# 5_motor_driver.net
KiCad netlist of a schematic drawn in Altium Designer
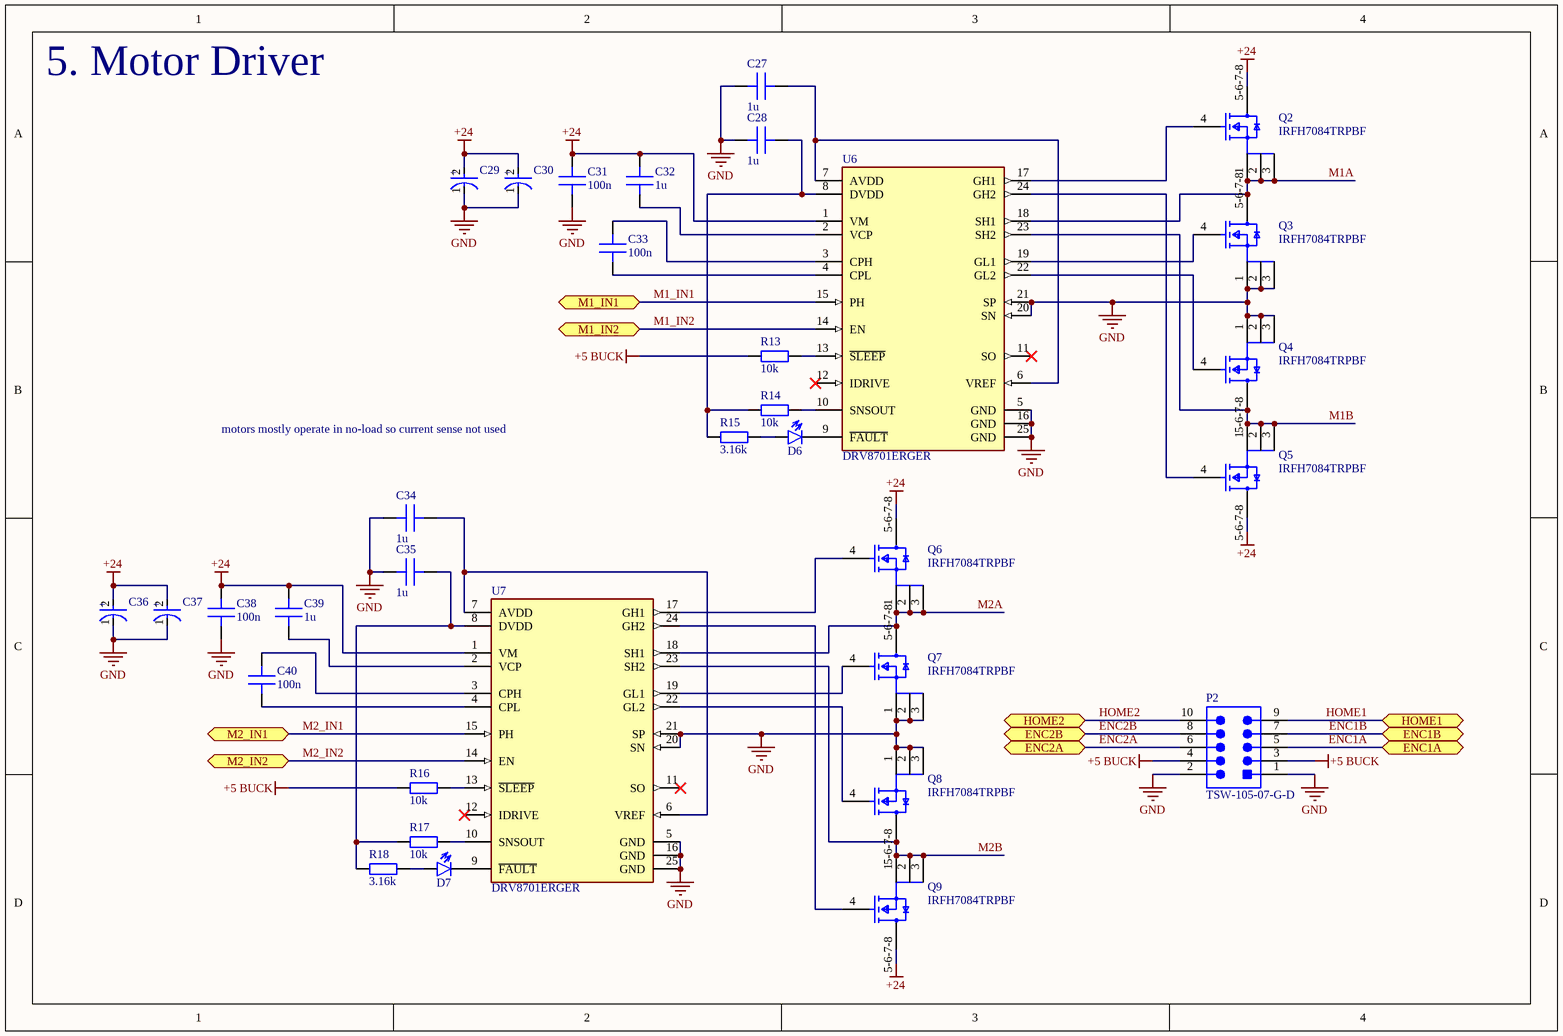
[diagram p0: 5_motor driver.SchDoc]

(export (version "E")
  (design (tool "Eeschema 10.0.6"))
  (components
    (comp (ref "C27")
      (value "1u")
      (footprint "IPC C C0402 NO SILK")
      (libsource (lib "JLCPCB Library") (part "Generic CAP 0402"))
    )
    (comp (ref "C28")
      (value "1u")
      (footprint "IPC C C0402 NO SILK")
      (libsource (lib "JLCPCB Library") (part "Generic CAP 0402"))
    )
    (comp (ref "C29")
      (value "UCW1H221MNL1GS")
      (footprint "FP-UCW1H221MNL1GS-MFG")
      (description "CAP ALUM 220UF 20% 50V SMD")
      (fields (field (name "TOLERANCE") "20%") (field (name "VOLTAGE") "50V"))
      (libsource (lib "Altium Content Vault") (part "cf48714ba7e38822c1575c7ec0b6d1f"))
    )
    (comp (ref "C30")
      (value "UCW1H221MNL1GS")
      (footprint "FP-UCW1H221MNL1GS-MFG")
      (description "CAP ALUM 220UF 20% 50V SMD")
      (fields (field (name "TOLERANCE") "20%") (field (name "VOLTAGE") "50V"))
      (libsource (lib "Altium Content Vault") (part "cf48714ba7e38822c1575c7ec0b6d1f"))
    )
    (comp (ref "C31")
      (value "100n")
      (footprint "IPC C C0603 NO SILK")
      (libsource (lib "JLCPCB Library") (part "Generic CAP 0603"))
    )
    (comp (ref "C32")
      (value "1u")
      (footprint "IPC C C0603 NO SILK")
      (libsource (lib "JLCPCB Library") (part "Generic CAP 0603"))
    )
    (comp (ref "C33")
      (value "100n")
      (footprint "IPC C C0603 NO SILK")
      (libsource (lib "JLCPCB Library") (part "Generic CAP 0603"))
    )
    (comp (ref "C34")
      (value "1u")
      (footprint "IPC C C0402 NO SILK")
      (libsource (lib "JLCPCB Library") (part "Generic CAP 0402"))
    )
    (comp (ref "C35")
      (value "1u")
      (footprint "IPC C C0402 NO SILK")
      (libsource (lib "JLCPCB Library") (part "Generic CAP 0402"))
    )
    (comp (ref "C36")
      (value "UCW1H221MNL1GS")
      (footprint "FP-UCW1H221MNL1GS-MFG")
      (description "CAP ALUM 220UF 20% 50V SMD")
      (fields (field (name "TOLERANCE") "20%") (field (name "VOLTAGE") "50V"))
      (libsource (lib "Altium Content Vault") (part "cf48714ba7e38822c1575c7ec0b6d1f"))
    )
    (comp (ref "C37")
      (value "UCW1H221MNL1GS")
      (footprint "FP-UCW1H221MNL1GS-MFG")
      (description "CAP ALUM 220UF 20% 50V SMD")
      (fields (field (name "TOLERANCE") "20%") (field (name "VOLTAGE") "50V"))
      (libsource (lib "Altium Content Vault") (part "cf48714ba7e38822c1575c7ec0b6d1f"))
    )
    (comp (ref "C38")
      (value "100n")
      (footprint "IPC C C0603 NO SILK")
      (libsource (lib "JLCPCB Library") (part "Generic CAP 0603"))
    )
    (comp (ref "C39")
      (value "1u")
      (footprint "IPC C C0603 NO SILK")
      (libsource (lib "JLCPCB Library") (part "Generic CAP 0603"))
    )
    (comp (ref "C40")
      (value "100n")
      (footprint "IPC C C0603 NO SILK")
      (libsource (lib "JLCPCB Library") (part "Generic CAP 0603"))
    )
    (comp (ref "D6")
      (value "Red LED 0603")
      (footprint "IPC C D0603")
      (libsource (lib "JLCPCB Library") (part "Generic LED 0603"))
    )
    (comp (ref "D7")
      (value "Red LED 0603")
      (footprint "IPC C D0603")
      (libsource (lib "JLCPCB Library") (part "Generic LED 0603"))
    )
    (comp (ref "P2")
      (value "TSW-105-07-G-D")
      (footprint "SMTC-TSW-105-07-G-D_V")
      (fields (field (name "MANUFACTURER") "Samtec-Inc."))
      (libsource (lib "Altium Content Vault") (part "CN-2P-M-R10"))
    )
    (comp (ref "Q2")
      (value "IRFH7084TRPBF")
      (footprint "FP-PQFN5x6-G-MFG")
      (description "MOSFET N-CH 40V 100A 8QFN")
      (libsource (lib "Altium Content Vault") (part "95ca5d46c4c8fe7d84c4fb5e2abfe3c"))
    )
    (comp (ref "Q3")
      (value "IRFH7084TRPBF")
      (footprint "FP-PQFN5x6-G-MFG")
      (description "MOSFET N-CH 40V 100A 8QFN")
      (libsource (lib "Altium Content Vault") (part "95ca5d46c4c8fe7d84c4fb5e2abfe3c"))
    )
    (comp (ref "Q4")
      (value "IRFH7084TRPBF")
      (footprint "FP-PQFN5x6-G-MFG")
      (description "MOSFET N-CH 40V 100A 8QFN")
      (libsource (lib "Altium Content Vault") (part "95ca5d46c4c8fe7d84c4fb5e2abfe3c"))
    )
    (comp (ref "Q5")
      (value "IRFH7084TRPBF")
      (footprint "FP-PQFN5x6-G-MFG")
      (description "MOSFET N-CH 40V 100A 8QFN")
      (libsource (lib "Altium Content Vault") (part "95ca5d46c4c8fe7d84c4fb5e2abfe3c"))
    )
    (comp (ref "Q6")
      (value "IRFH7084TRPBF")
      (footprint "FP-PQFN5x6-G-MFG")
      (description "MOSFET N-CH 40V 100A 8QFN")
      (libsource (lib "Altium Content Vault") (part "95ca5d46c4c8fe7d84c4fb5e2abfe3c"))
    )
    (comp (ref "Q7")
      (value "IRFH7084TRPBF")
      (footprint "FP-PQFN5x6-G-MFG")
      (description "MOSFET N-CH 40V 100A 8QFN")
      (libsource (lib "Altium Content Vault") (part "95ca5d46c4c8fe7d84c4fb5e2abfe3c"))
    )
    (comp (ref "Q8")
      (value "IRFH7084TRPBF")
      (footprint "FP-PQFN5x6-G-MFG")
      (description "MOSFET N-CH 40V 100A 8QFN")
      (libsource (lib "Altium Content Vault") (part "95ca5d46c4c8fe7d84c4fb5e2abfe3c"))
    )
    (comp (ref "Q9")
      (value "IRFH7084TRPBF")
      (footprint "FP-PQFN5x6-G-MFG")
      (description "MOSFET N-CH 40V 100A 8QFN")
      (libsource (lib "Altium Content Vault") (part "95ca5d46c4c8fe7d84c4fb5e2abfe3c"))
    )
    (comp (ref "R13")
      (value "10k")
      (footprint "IPC C R0402 NO SILK")
      (libsource (lib "JLCPCB Library") (part "Generic RES 0402"))
    )
    (comp (ref "R14")
      (value "10k")
      (footprint "IPC C R0402 NO SILK")
      (libsource (lib "JLCPCB Library") (part "Generic RES 0402"))
    )
    (comp (ref "R15")
      (value "3.16k")
      (footprint "IPC C R0402 NO SILK")
      (libsource (lib "JLCPCB Library") (part "Generic RES 0402"))
    )
    (comp (ref "R16")
      (value "10k")
      (footprint "IPC C R0402 NO SILK")
      (libsource (lib "JLCPCB Library") (part "Generic RES 0402"))
    )
    (comp (ref "R17")
      (value "10k")
      (footprint "IPC C R0402 NO SILK")
      (libsource (lib "JLCPCB Library") (part "Generic RES 0402"))
    )
    (comp (ref "R18")
      (value "3.16k")
      (footprint "IPC C R0402 NO SILK")
      (libsource (lib "JLCPCB Library") (part "Generic RES 0402"))
    )
    (comp (ref "U6")
      (value "DRV8701ERGER")
      (footprint "FP-RGE0024F-MFG")
      (description "IC MOTOR DRIVER 0V-5.5V 24VQFN")
      (libsource (lib "Altium Content Vault") (part "52b49e6391ebd4280530f99f160d6ab"))
    )
    (comp (ref "U7")
      (value "DRV8701ERGER")
      (footprint "FP-RGE0024F-MFG")
      (description "IC MOTOR DRIVER 0V-5.5V 24VQFN")
      (libsource (lib "Altium Content Vault") (part "52b49e6391ebd4280530f99f160d6ab"))
    )
  )
  (nets
    (net (code "1") (name "+5 BUCK") (class "Default")
      (node (ref "P2") (pin "3") (pinfunction "3_3") (pintype "passive"))
      (node (ref "P2") (pin "4") (pinfunction "4_4") (pintype "passive"))
      (node (ref "R13") (pin "2") (pinfunction "2_2") (pintype "passive"))
      (node (ref "R16") (pin "2") (pinfunction "2_2") (pintype "passive"))
    )
    (net (code "2") (name "+24") (class "Default")
      (node (ref "C29") (pin "2") (pinfunction "A_2") (pintype "passive"))
      (node (ref "C30") (pin "2") (pinfunction "A_2") (pintype "passive"))
      (node (ref "C31") (pin "2") (pinfunction "2_2") (pintype "passive"))
      (node (ref "C32") (pin "1") (pinfunction "1_1") (pintype "passive"))
      (node (ref "C36") (pin "2") (pinfunction "A_2") (pintype "passive"))
      (node (ref "C37") (pin "2") (pinfunction "A_2") (pintype "passive"))
      (node (ref "C38") (pin "2") (pinfunction "2_2") (pintype "passive"))
      (node (ref "C39") (pin "1") (pinfunction "1_1") (pintype "passive"))
      (node (ref "Q2") (pin "5-6-7-8") (pinfunction "D_5-6-7-8") (pintype "passive"))
      (node (ref "Q5") (pin "5-6-7-8") (pinfunction "D_5-6-7-8") (pintype "passive"))
      (node (ref "Q6") (pin "5-6-7-8") (pinfunction "D_5-6-7-8") (pintype "passive"))
      (node (ref "Q9") (pin "5-6-7-8") (pinfunction "D_5-6-7-8") (pintype "passive"))
      (node (ref "U6") (pin "1") (pinfunction "VM_1") (pintype "power_in"))
      (node (ref "U7") (pin "1") (pinfunction "VM_1") (pintype "power_in"))
    )
    (net (code "3") (name "/ENC1A") (class "Default")
      (node (ref "P2") (pin "5") (pinfunction "5_5") (pintype "passive"))
    )
    (net (code "4") (name "/ENC1B") (class "Default")
      (node (ref "P2") (pin "7") (pinfunction "7_7") (pintype "passive"))
    )
    (net (code "5") (name "/ENC2A") (class "Default")
      (node (ref "P2") (pin "6") (pinfunction "6_6") (pintype "passive"))
    )
    (net (code "6") (name "/ENC2B") (class "Default")
      (node (ref "P2") (pin "8") (pinfunction "8_8") (pintype "passive"))
    )
    (net (code "7") (name "/HOME1") (class "Default")
      (node (ref "P2") (pin "9") (pinfunction "9_9") (pintype "passive"))
    )
    (net (code "8") (name "/HOME2") (class "Default")
      (node (ref "P2") (pin "10") (pinfunction "10_10") (pintype "passive"))
    )
    (net (code "9") (name "/M1A") (class "Default")
      (node (ref "Q2") (pin "1") (pinfunction "S_1") (pintype "passive"))
      (node (ref "Q2") (pin "2") (pinfunction "S_2") (pintype "passive"))
      (node (ref "Q2") (pin "3") (pinfunction "S_3") (pintype "passive"))
      (node (ref "Q3") (pin "5-6-7-8") (pinfunction "D_5-6-7-8") (pintype "passive"))
      (node (ref "U6") (pin "18") (pinfunction "SH1_18") (pintype "output"))
    )
    (net (code "10") (name "/M1B") (class "Default")
      (node (ref "Q4") (pin "5-6-7-8") (pinfunction "D_5-6-7-8") (pintype "passive"))
      (node (ref "Q5") (pin "1") (pinfunction "S_1") (pintype "passive"))
      (node (ref "Q5") (pin "2") (pinfunction "S_2") (pintype "passive"))
      (node (ref "Q5") (pin "3") (pinfunction "S_3") (pintype "passive"))
      (node (ref "U6") (pin "23") (pinfunction "SH2_23") (pintype "output"))
    )
    (net (code "11") (name "/M1_IN1") (class "Default")
      (node (ref "U6") (pin "15") (pinfunction "PH_15") (pintype "input"))
    )
    (net (code "12") (name "/M1_IN2") (class "Default")
      (node (ref "U6") (pin "14") (pinfunction "EN_14") (pintype "input"))
    )
    (net (code "13") (name "/M2A") (class "Default")
      (node (ref "Q6") (pin "1") (pinfunction "S_1") (pintype "passive"))
      (node (ref "Q6") (pin "2") (pinfunction "S_2") (pintype "passive"))
      (node (ref "Q6") (pin "3") (pinfunction "S_3") (pintype "passive"))
      (node (ref "Q7") (pin "5-6-7-8") (pinfunction "D_5-6-7-8") (pintype "passive"))
      (node (ref "U7") (pin "18") (pinfunction "SH1_18") (pintype "output"))
    )
    (net (code "14") (name "/M2B") (class "Default")
      (node (ref "Q8") (pin "5-6-7-8") (pinfunction "D_5-6-7-8") (pintype "passive"))
      (node (ref "Q9") (pin "1") (pinfunction "S_1") (pintype "passive"))
      (node (ref "Q9") (pin "2") (pinfunction "S_2") (pintype "passive"))
      (node (ref "Q9") (pin "3") (pinfunction "S_3") (pintype "passive"))
      (node (ref "U7") (pin "23") (pinfunction "SH2_23") (pintype "output"))
    )
    (net (code "15") (name "/M2_IN1") (class "Default")
      (node (ref "U7") (pin "15") (pinfunction "PH_15") (pintype "input"))
    )
    (net (code "16") (name "/M2_IN2") (class "Default")
      (node (ref "U7") (pin "14") (pinfunction "EN_14") (pintype "input"))
    )
    (net (code "17") (name "GND") (class "Default")
      (node (ref "C27") (pin "1") (pinfunction "1_1") (pintype "passive"))
      (node (ref "C28") (pin "1") (pinfunction "1_1") (pintype "passive"))
      (node (ref "C29") (pin "1") (pinfunction "C_1") (pintype "passive"))
      (node (ref "C30") (pin "1") (pinfunction "C_1") (pintype "passive"))
      (node (ref "C31") (pin "1") (pinfunction "1_1") (pintype "passive"))
      (node (ref "C34") (pin "1") (pinfunction "1_1") (pintype "passive"))
      (node (ref "C35") (pin "1") (pinfunction "1_1") (pintype "passive"))
      (node (ref "C36") (pin "1") (pinfunction "C_1") (pintype "passive"))
      (node (ref "C37") (pin "1") (pinfunction "C_1") (pintype "passive"))
      (node (ref "C38") (pin "1") (pinfunction "1_1") (pintype "passive"))
      (node (ref "P2") (pin "1") (pinfunction "1_1") (pintype "passive"))
      (node (ref "P2") (pin "2") (pinfunction "2_2") (pintype "passive"))
      (node (ref "Q3") (pin "1") (pinfunction "S_1") (pintype "passive"))
      (node (ref "Q3") (pin "2") (pinfunction "S_2") (pintype "passive"))
      (node (ref "Q3") (pin "3") (pinfunction "S_3") (pintype "passive"))
      (node (ref "Q4") (pin "1") (pinfunction "S_1") (pintype "passive"))
      (node (ref "Q4") (pin "2") (pinfunction "S_2") (pintype "passive"))
      (node (ref "Q4") (pin "3") (pinfunction "S_3") (pintype "passive"))
      (node (ref "Q7") (pin "1") (pinfunction "S_1") (pintype "passive"))
      (node (ref "Q7") (pin "2") (pinfunction "S_2") (pintype "passive"))
      (node (ref "Q7") (pin "3") (pinfunction "S_3") (pintype "passive"))
      (node (ref "Q8") (pin "1") (pinfunction "S_1") (pintype "passive"))
      (node (ref "Q8") (pin "2") (pinfunction "S_2") (pintype "passive"))
      (node (ref "Q8") (pin "3") (pinfunction "S_3") (pintype "passive"))
      (node (ref "U6") (pin "16") (pinfunction "GND_16") (pintype "power_in"))
      (node (ref "U6") (pin "20") (pinfunction "SN_20") (pintype "input"))
      (node (ref "U6") (pin "21") (pinfunction "SP_21") (pintype "input"))
      (node (ref "U6") (pin "25") (pinfunction "GND_25") (pintype "power_in"))
      (node (ref "U6") (pin "5") (pinfunction "GND_5") (pintype "power_in"))
      (node (ref "U7") (pin "16") (pinfunction "GND_16") (pintype "power_in"))
      (node (ref "U7") (pin "20") (pinfunction "SN_20") (pintype "input"))
      (node (ref "U7") (pin "21") (pinfunction "SP_21") (pintype "input"))
      (node (ref "U7") (pin "25") (pinfunction "GND_25") (pintype "power_in"))
      (node (ref "U7") (pin "5") (pinfunction "GND_5") (pintype "power_in"))
    )
    (net (code "18") (name "Net-(D6-A)") (class "Default")
      (node (ref "D6") (pin "1") (pinfunction "A_1") (pintype "passive"))
      (node (ref "R15") (pin "1") (pinfunction "1_1") (pintype "passive"))
    )
    (net (code "19") (name "Net-(D6-C)") (class "Default")
      (node (ref "D6") (pin "2") (pinfunction "C_2") (pintype "passive"))
      (node (ref "U6") (pin "9") (pinfunction "~{FAULT}_9") (pintype "open_emitter"))
    )
    (net (code "20") (name "Net-(D7-A)") (class "Default")
      (node (ref "D7") (pin "1") (pinfunction "A_1") (pintype "passive"))
      (node (ref "R18") (pin "1") (pinfunction "1_1") (pintype "passive"))
    )
    (net (code "21") (name "Net-(D7-C)") (class "Default")
      (node (ref "D7") (pin "2") (pinfunction "C_2") (pintype "passive"))
      (node (ref "U7") (pin "9") (pinfunction "~{FAULT}_9") (pintype "open_emitter"))
    )
    (net (code "22") (name "Net-(Q2-G)") (class "Default")
      (node (ref "Q2") (pin "4") (pinfunction "G_4") (pintype "passive"))
      (node (ref "U6") (pin "17") (pinfunction "GH1_17") (pintype "output"))
    )
    (net (code "23") (name "Net-(Q3-G)") (class "Default")
      (node (ref "Q3") (pin "4") (pinfunction "G_4") (pintype "passive"))
      (node (ref "U6") (pin "19") (pinfunction "GL1_19") (pintype "output"))
    )
    (net (code "24") (name "Net-(Q4-G)") (class "Default")
      (node (ref "Q4") (pin "4") (pinfunction "G_4") (pintype "passive"))
      (node (ref "U6") (pin "22") (pinfunction "GL2_22") (pintype "output"))
    )
    (net (code "25") (name "Net-(Q5-G)") (class "Default")
      (node (ref "Q5") (pin "4") (pinfunction "G_4") (pintype "passive"))
      (node (ref "U6") (pin "24") (pinfunction "GH2_24") (pintype "output"))
    )
    (net (code "26") (name "Net-(Q6-G)") (class "Default")
      (node (ref "Q6") (pin "4") (pinfunction "G_4") (pintype "passive"))
      (node (ref "U7") (pin "17") (pinfunction "GH1_17") (pintype "output"))
    )
    (net (code "27") (name "Net-(Q7-G)") (class "Default")
      (node (ref "Q7") (pin "4") (pinfunction "G_4") (pintype "passive"))
      (node (ref "U7") (pin "19") (pinfunction "GL1_19") (pintype "output"))
    )
    (net (code "28") (name "Net-(Q8-G)") (class "Default")
      (node (ref "Q8") (pin "4") (pinfunction "G_4") (pintype "passive"))
      (node (ref "U7") (pin "22") (pinfunction "GL2_22") (pintype "output"))
    )
    (net (code "29") (name "Net-(Q9-G)") (class "Default")
      (node (ref "Q9") (pin "4") (pinfunction "G_4") (pintype "passive"))
      (node (ref "U7") (pin "24") (pinfunction "GH2_24") (pintype "output"))
    )
    (net (code "30") (name "Net-(U6-AVDD)") (class "Default")
      (node (ref "C27") (pin "2") (pinfunction "2_2") (pintype "passive"))
      (node (ref "U6") (pin "6") (pinfunction "VREF_6") (pintype "input"))
      (node (ref "U6") (pin "7") (pinfunction "AVDD_7") (pintype "power_in"))
    )
    (net (code "31") (name "Net-(U6-CPH)") (class "Default")
      (node (ref "C33") (pin "1") (pinfunction "1_1") (pintype "passive"))
      (node (ref "U6") (pin "3") (pinfunction "CPH_3") (pintype "power_in"))
    )
    (net (code "32") (name "Net-(U6-CPL)") (class "Default")
      (node (ref "C33") (pin "2") (pinfunction "2_2") (pintype "passive"))
      (node (ref "U6") (pin "4") (pinfunction "CPL_4") (pintype "power_in"))
    )
    (net (code "33") (name "Net-(U6-DVDD)") (class "Default")
      (node (ref "C28") (pin "2") (pinfunction "2_2") (pintype "passive"))
      (node (ref "R14") (pin "2") (pinfunction "2_2") (pintype "passive"))
      (node (ref "R15") (pin "2") (pinfunction "2_2") (pintype "passive"))
      (node (ref "U6") (pin "8") (pinfunction "DVDD_8") (pintype "power_in"))
    )
    (net (code "34") (name "Net-(U6-SNSOUT)") (class "Default")
      (node (ref "R14") (pin "1") (pinfunction "1_1") (pintype "passive"))
      (node (ref "U6") (pin "10") (pinfunction "SNSOUT_10") (pintype "open_emitter"))
    )
    (net (code "35") (name "Net-(U6-VCP)") (class "Default")
      (node (ref "C32") (pin "2") (pinfunction "2_2") (pintype "passive"))
      (node (ref "U6") (pin "2") (pinfunction "VCP_2") (pintype "power_in"))
    )
    (net (code "36") (name "Net-(U6-~{SLEEP})") (class "Default")
      (node (ref "R13") (pin "1") (pinfunction "1_1") (pintype "passive"))
      (node (ref "U6") (pin "13") (pinfunction "~{SLEEP}_13") (pintype "input"))
    )
    (net (code "37") (name "Net-(U7-AVDD)") (class "Default")
      (node (ref "C34") (pin "2") (pinfunction "2_2") (pintype "passive"))
      (node (ref "U7") (pin "6") (pinfunction "VREF_6") (pintype "input"))
      (node (ref "U7") (pin "7") (pinfunction "AVDD_7") (pintype "power_in"))
    )
    (net (code "38") (name "Net-(U7-CPH)") (class "Default")
      (node (ref "C40") (pin "1") (pinfunction "1_1") (pintype "passive"))
      (node (ref "U7") (pin "3") (pinfunction "CPH_3") (pintype "power_in"))
    )
    (net (code "39") (name "Net-(U7-CPL)") (class "Default")
      (node (ref "C40") (pin "2") (pinfunction "2_2") (pintype "passive"))
      (node (ref "U7") (pin "4") (pinfunction "CPL_4") (pintype "power_in"))
    )
    (net (code "40") (name "Net-(U7-DVDD)") (class "Default")
      (node (ref "C35") (pin "2") (pinfunction "2_2") (pintype "passive"))
      (node (ref "R17") (pin "2") (pinfunction "2_2") (pintype "passive"))
      (node (ref "R18") (pin "2") (pinfunction "2_2") (pintype "passive"))
      (node (ref "U7") (pin "8") (pinfunction "DVDD_8") (pintype "power_in"))
    )
    (net (code "41") (name "Net-(U7-SNSOUT)") (class "Default")
      (node (ref "R17") (pin "1") (pinfunction "1_1") (pintype "passive"))
      (node (ref "U7") (pin "10") (pinfunction "SNSOUT_10") (pintype "open_emitter"))
    )
    (net (code "42") (name "Net-(U7-VCP)") (class "Default")
      (node (ref "C39") (pin "2") (pinfunction "2_2") (pintype "passive"))
      (node (ref "U7") (pin "2") (pinfunction "VCP_2") (pintype "power_in"))
    )
    (net (code "43") (name "Net-(U7-~{SLEEP})") (class "Default")
      (node (ref "R16") (pin "1") (pinfunction "1_1") (pintype "passive"))
      (node (ref "U7") (pin "13") (pinfunction "~{SLEEP}_13") (pintype "input"))
    )
    (net (code "44") (name "unconnected-(U6-IDRIVE-Pad12)") (class "Default")
      (node (ref "U6") (pin "12") (pinfunction "IDRIVE_12") (pintype "input+no_connect"))
    )
    (net (code "45") (name "unconnected-(U6-SO-Pad11)") (class "Default")
      (node (ref "U6") (pin "11") (pinfunction "SO_11") (pintype "output+no_connect"))
    )
    (net (code "46") (name "unconnected-(U7-IDRIVE-Pad12)") (class "Default")
      (node (ref "U7") (pin "12") (pinfunction "IDRIVE_12") (pintype "input+no_connect"))
    )
    (net (code "47") (name "unconnected-(U7-SO-Pad11)") (class "Default")
      (node (ref "U7") (pin "11") (pinfunction "SO_11") (pintype "output+no_connect"))
    )
  )
)
